# Main_circuit.net
KiCad netlist of a schematic drawn in Altium Designer
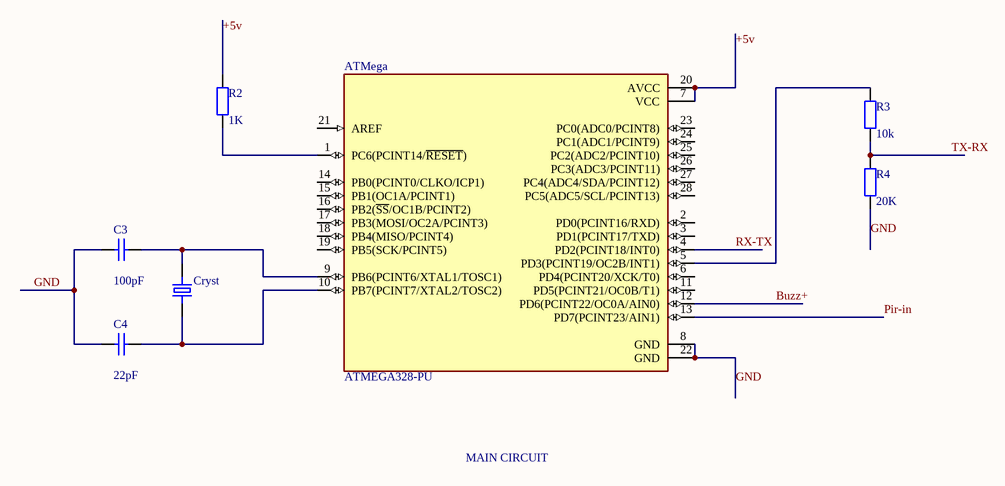
[diagram p0: Main circuit.SchDoc]

(export (version "E")
  (design (tool "Eeschema 10.0.6"))
  (components
    (comp (ref "ATMega")
      (value "ATMEGA328-PU")
      (footprint "DIP787W46P254L3467H508Q28")
      (description "AVR AVRÂ® ATmega Microcontroller IC 8-Bit 20MHz 32KB (16K x 16) FLASH 28-PDIP")
      (libsource (lib "ATMEGA328-PU") (part "ATMEGA328-PU"))
    )
    (comp (ref "C3")
      (value "100pF")
      (footprint "RAD-0.3")
      (description "Capacitor")
      (fields (field (name "Comment") "Cap") (field (name "PUBLISHER") "Altium Limited"))
      (libsource (lib "Miscellaneous Devices") (part "Cap"))
    )
    (comp (ref "C4")
      (value "22pF")
      (footprint "RAD-0.3")
      (description "Capacitor")
      (fields (field (name "Comment") "Cap") (field (name "PUBLISHER") "Altium Limited"))
      (libsource (lib "Miscellaneous Devices") (part "Cap"))
    )
    (comp (ref "Cryst")
      (value "ECS-160-S-4")
      (footprint "XTAL_ECS-160-20-4X")
      (description "16MHz Â±30ppm Crystal Series 40 Ohms HC-49/US")
      (fields (field (name "MF") "ECS Inc."))
      (libsource (lib "ECS-160-S-4") (part "ECS-160-S-4"))
    )
    (comp (ref "R2")
      (value "1K")
      (footprint "AXIAL-0.4")
      (description "Resistor")
      (fields (field (name "Comment") "Res2") (field (name "PUBLISHER") "Altium Limited"))
      (libsource (lib "Miscellaneous Devices") (part "Res2"))
    )
    (comp (ref "R3")
      (value "10k")
      (footprint "AXIAL-0.4")
      (description "Resistor")
      (fields (field (name "Comment") "Res2") (field (name "PUBLISHER") "Altium Limited"))
      (libsource (lib "Miscellaneous Devices") (part "Res2"))
    )
    (comp (ref "R4")
      (value "20K")
      (footprint "AXIAL-0.4")
      (description "Resistor")
      (fields (field (name "Comment") "Res2") (field (name "PUBLISHER") "Altium Limited"))
      (libsource (lib "Miscellaneous Devices") (part "Res2"))
    )
  )
  (nets
    (net (code "1") (name "/+5v") (class "Default")
      (node (ref "ATMega") (pin "20") (pinfunction "AVCC_20") (pintype "power_in"))
      (node (ref "ATMega") (pin "7") (pinfunction "VCC_7") (pintype "power_in"))
      (node (ref "R2") (pin "2") (pinfunction "2_2") (pintype "passive"))
    )
    (net (code "2") (name "/Buzz+") (class "Default")
      (node (ref "ATMega") (pin "12") (pinfunction "PD6(PCINT22/OC0A/AIN0)_12") (pintype "bidirectional"))
    )
    (net (code "3") (name "/GND") (class "Default")
      (node (ref "ATMega") (pin "22") (pinfunction "GND_22") (pintype "power_in"))
      (node (ref "ATMega") (pin "8") (pinfunction "GND_8") (pintype "power_in"))
      (node (ref "C3") (pin "1") (pinfunction "1_1") (pintype "passive"))
      (node (ref "C4") (pin "1") (pinfunction "1_1") (pintype "passive"))
      (node (ref "R4") (pin "1") (pinfunction "1_1") (pintype "passive"))
    )
    (net (code "4") (name "/Pir-in") (class "Default")
      (node (ref "ATMega") (pin "13") (pinfunction "PD7(PCINT23/AIN1)_13") (pintype "bidirectional"))
    )
    (net (code "5") (name "/RX-TX") (class "Default")
      (node (ref "ATMega") (pin "4") (pinfunction "PD2(PCINT18/INT0)_4") (pintype "bidirectional"))
    )
    (net (code "6") (name "/TX-RX") (class "Default")
      (node (ref "R3") (pin "1") (pinfunction "1_1") (pintype "passive"))
      (node (ref "R4") (pin "2") (pinfunction "2_2") (pintype "passive"))
    )
    (net (code "7") (name "Net-(ATMega-PB6(PCINT6{slash}XTAL1{slash}TOSC1))") (class "Default")
      (node (ref "ATMega") (pin "9") (pinfunction "PB6(PCINT6/XTAL1/TOSC1)_9") (pintype "bidirectional"))
      (node (ref "C3") (pin "2") (pinfunction "2_2") (pintype "passive"))
      (node (ref "Cryst") (pin "2") (pinfunction "2_2") (pintype "passive"))
    )
    (net (code "8") (name "Net-(ATMega-PB7(PCINT7{slash}XTAL2{slash}TOSC2))") (class "Default")
      (node (ref "ATMega") (pin "10") (pinfunction "PB7(PCINT7/XTAL2/TOSC2)_10") (pintype "bidirectional"))
      (node (ref "C4") (pin "2") (pinfunction "2_2") (pintype "passive"))
      (node (ref "Cryst") (pin "1") (pinfunction "1_1") (pintype "passive"))
    )
    (net (code "9") (name "Net-(ATMega-PC6(PCINT14{slash}~{RESET}))") (class "Default")
      (node (ref "ATMega") (pin "1") (pinfunction "PC6(PCINT14/~{RESET})_1") (pintype "bidirectional"))
      (node (ref "R2") (pin "1") (pinfunction "1_1") (pintype "passive"))
    )
    (net (code "10") (name "Net-(ATMega-PD3(PCINT19{slash}OC2B{slash}INT1))") (class "Default")
      (node (ref "ATMega") (pin "5") (pinfunction "PD3(PCINT19/OC2B/INT1)_5") (pintype "bidirectional"))
      (node (ref "R3") (pin "2") (pinfunction "2_2") (pintype "passive"))
    )
    (net (code "11") (name "unconnected-(ATMega-AREF-Pad21)") (class "Default")
      (node (ref "ATMega") (pin "21") (pinfunction "AREF_21") (pintype "input"))
    )
    (net (code "12") (name "unconnected-(ATMega-PB0(PCINT0{slash}CLKO{slash}ICP1)-Pad14)") (class "Default")
      (node (ref "ATMega") (pin "14") (pinfunction "PB0(PCINT0/CLKO/ICP1)_14") (pintype "bidirectional"))
    )
    (net (code "13") (name "unconnected-(ATMega-PB1(OC1A{slash}PCINT1)-Pad15)") (class "Default")
      (node (ref "ATMega") (pin "15") (pinfunction "PB1(OC1A/PCINT1)_15") (pintype "bidirectional"))
    )
    (net (code "14") (name "unconnected-(ATMega-PB2(~{SS}{slash}OC1B{slash}PCINT2)-Pad16)") (class "Default")
      (node (ref "ATMega") (pin "16") (pinfunction "PB2(~{SS}/OC1B/PCINT2)_16") (pintype "bidirectional"))
    )
    (net (code "15") (name "unconnected-(ATMega-PB3(MOSI{slash}OC2A{slash}PCINT3)-Pad17)") (class "Default")
      (node (ref "ATMega") (pin "17") (pinfunction "PB3(MOSI/OC2A/PCINT3)_17") (pintype "bidirectional"))
    )
    (net (code "16") (name "unconnected-(ATMega-PB4(MISO{slash}PCINT4)-Pad18)") (class "Default")
      (node (ref "ATMega") (pin "18") (pinfunction "PB4(MISO/PCINT4)_18") (pintype "bidirectional"))
    )
    (net (code "17") (name "unconnected-(ATMega-PB5(SCK{slash}PCINT5)-Pad19)") (class "Default")
      (node (ref "ATMega") (pin "19") (pinfunction "PB5(SCK/PCINT5)_19") (pintype "bidirectional"))
    )
    (net (code "18") (name "unconnected-(ATMega-PC0(ADC0{slash}PCINT8)-Pad23)") (class "Default")
      (node (ref "ATMega") (pin "23") (pinfunction "PC0(ADC0/PCINT8)_23") (pintype "bidirectional"))
    )
    (net (code "19") (name "unconnected-(ATMega-PC1(ADC1{slash}PCINT9)-Pad24)") (class "Default")
      (node (ref "ATMega") (pin "24") (pinfunction "PC1(ADC1/PCINT9)_24") (pintype "bidirectional"))
    )
    (net (code "20") (name "unconnected-(ATMega-PC2(ADC2{slash}PCINT10)-Pad25)") (class "Default")
      (node (ref "ATMega") (pin "25") (pinfunction "PC2(ADC2/PCINT10)_25") (pintype "bidirectional"))
    )
    (net (code "21") (name "unconnected-(ATMega-PC3(ADC3{slash}PCINT11)-Pad26)") (class "Default")
      (node (ref "ATMega") (pin "26") (pinfunction "PC3(ADC3/PCINT11)_26") (pintype "bidirectional"))
    )
    (net (code "22") (name "unconnected-(ATMega-PC4(ADC4{slash}SDA{slash}PCINT12)-Pad27)") (class "Default")
      (node (ref "ATMega") (pin "27") (pinfunction "PC4(ADC4/SDA/PCINT12)_27") (pintype "bidirectional"))
    )
    (net (code "23") (name "unconnected-(ATMega-PC5(ADC5{slash}SCL{slash}PCINT13)-Pad28)") (class "Default")
      (node (ref "ATMega") (pin "28") (pinfunction "PC5(ADC5/SCL/PCINT13)_28") (pintype "bidirectional"))
    )
    (net (code "24") (name "unconnected-(ATMega-PD0(PCINT16{slash}RXD)-Pad2)") (class "Default")
      (node (ref "ATMega") (pin "2") (pinfunction "PD0(PCINT16/RXD)_2") (pintype "bidirectional"))
    )
    (net (code "25") (name "unconnected-(ATMega-PD1(PCINT17{slash}TXD)-Pad3)") (class "Default")
      (node (ref "ATMega") (pin "3") (pinfunction "PD1(PCINT17/TXD)_3") (pintype "bidirectional"))
    )
    (net (code "26") (name "unconnected-(ATMega-PD4(PCINT20{slash}XCK{slash}T0)-Pad6)") (class "Default")
      (node (ref "ATMega") (pin "6") (pinfunction "PD4(PCINT20/XCK/T0)_6") (pintype "bidirectional"))
    )
    (net (code "27") (name "unconnected-(ATMega-PD5(PCINT21{slash}OC0B{slash}T1)-Pad11)") (class "Default")
      (node (ref "ATMega") (pin "11") (pinfunction "PD5(PCINT21/OC0B/T1)_11") (pintype "bidirectional"))
    )
  )
)
